# PowerWaveyRadar.net
KiCad netlist of a schematic drawn in Altium Designer
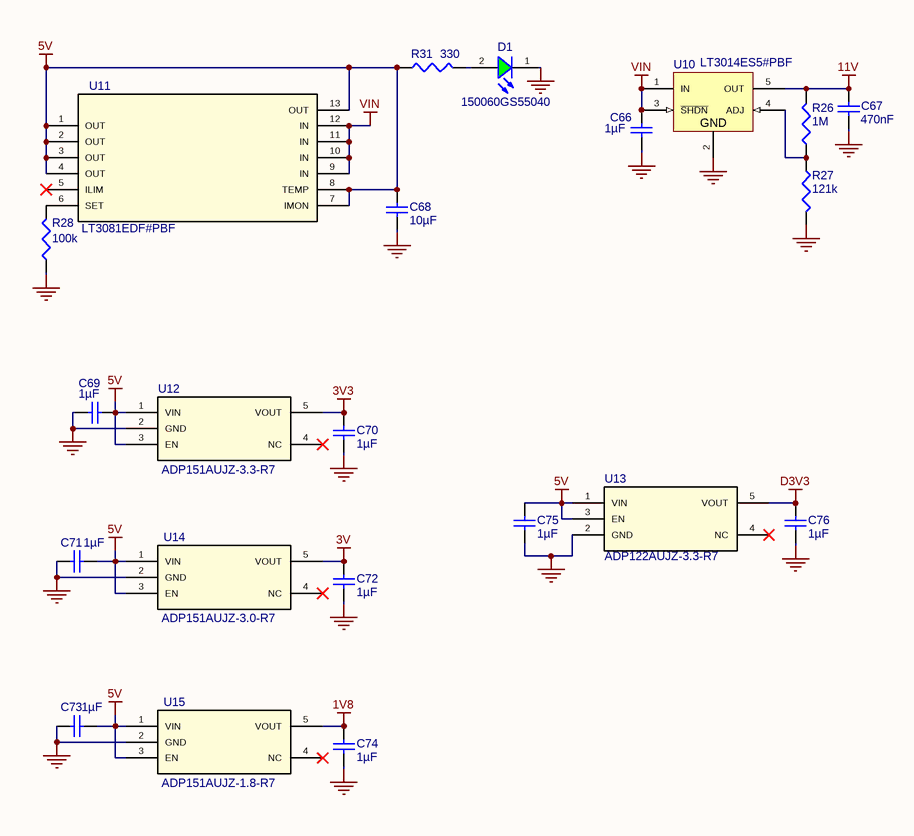
[diagram p0: PowerWaveyRadar.SchDoc]

(export (version "E")
  (design (tool "Eeschema 10.0.6"))
  (components
    (comp (ref "C66")
      (value "1µF")
      (footprint "CAPC0402(1005)60_L")
      (description "Chip Capacitor, 1µF +/-20%, 10V, 0402, Thickness 0.6 mm")
      (fields (field (name "TOLERANCE") "10%") (field (name "Comment") "Capacitor 1µF +/-20% 10V 0402"))
      (libsource (lib "University of South Florida") (part "CAP-NP-2"))
    )
    (comp (ref "C67")
      (value "470nF")
      (footprint "CAPC0402(1005)60_L")
      (description "Chip Capacitor, 470nF +/-40%, 10V, 0402, Thickness 0.6 mm")
      (fields (field (name "TOLERANCE") "20%") (field (name "Comment") "Capacitor 470nF +/-40% 10V 0402"))
      (libsource (lib "University of South Florida") (part "CAP-NP-2"))
    )
    (comp (ref "C68")
      (value "10µF")
      (footprint "CAPC0402(1005)60_L")
      (description "Chip Capacitor, 10µF +/-40%, 6.3V, 0402, Thickness 0.6 mm")
      (fields (field (name "TOLERANCE") "10%") (field (name "Comment") "Capacitor 10µF +/-40% 6.3V 0402"))
      (libsource (lib "University of South Florida") (part "CAP-NP-2"))
    )
    (comp (ref "C69")
      (value "1µF")
      (footprint "CAPC0402(1005)60_L")
      (description "Chip Capacitor, 1µF +/-20%, 10V, 0402, Thickness 0.6 mm")
      (fields (field (name "TOLERANCE") "10%") (field (name "Comment") "Capacitor 1µF +/-20% 10V 0402"))
      (libsource (lib "University of South Florida") (part "CAP-NP-2"))
    )
    (comp (ref "C70")
      (value "1µF")
      (footprint "CAPC0402(1005)60_L")
      (description "Chip Capacitor, 1µF +/-20%, 10V, 0402, Thickness 0.6 mm")
      (fields (field (name "TOLERANCE") "10%") (field (name "Comment") "Capacitor 1µF +/-20% 10V 0402"))
      (libsource (lib "University of South Florida") (part "CAP-NP-2"))
    )
    (comp (ref "C71")
      (value "1µF")
      (footprint "CAPC0402(1005)60_L")
      (description "Chip Capacitor, 1µF +/-20%, 10V, 0402, Thickness 0.6 mm")
      (fields (field (name "TOLERANCE") "10%") (field (name "Comment") "Capacitor 1µF +/-20% 10V 0402"))
      (libsource (lib "University of South Florida") (part "CAP-NP-2"))
    )
    (comp (ref "C72")
      (value "1µF")
      (footprint "CAPC0402(1005)60_L")
      (description "Chip Capacitor, 1µF +/-20%, 10V, 0402, Thickness 0.6 mm")
      (fields (field (name "TOLERANCE") "10%") (field (name "Comment") "Capacitor 1µF +/-20% 10V 0402"))
      (libsource (lib "University of South Florida") (part "CAP-NP-2"))
    )
    (comp (ref "C73")
      (value "1µF")
      (footprint "CAPC0402(1005)60_L")
      (description "Chip Capacitor, 1µF +/-20%, 10V, 0402, Thickness 0.6 mm")
      (fields (field (name "TOLERANCE") "10%") (field (name "Comment") "Capacitor 1µF +/-20% 10V 0402"))
      (libsource (lib "University of South Florida") (part "CAP-NP-2"))
    )
    (comp (ref "C74")
      (value "1µF")
      (footprint "CAPC0402(1005)60_L")
      (description "Chip Capacitor, 1µF +/-20%, 10V, 0402, Thickness 0.6 mm")
      (fields (field (name "TOLERANCE") "10%") (field (name "Comment") "Capacitor 1µF +/-20% 10V 0402"))
      (libsource (lib "University of South Florida") (part "CAP-NP-2"))
    )
    (comp (ref "C75")
      (value "1µF")
      (footprint "CAPC0402(1005)60_L")
      (description "Chip Capacitor, 1µF +/-20%, 10V, 0402, Thickness 0.6 mm")
      (fields (field (name "TOLERANCE") "10%") (field (name "Comment") "Capacitor 1µF +/-20% 10V 0402"))
      (libsource (lib "University of South Florida") (part "CAP-NP-2"))
    )
    (comp (ref "C76")
      (value "1µF")
      (footprint "CAPC0402(1005)60_L")
      (description "Chip Capacitor, 1µF +/-20%, 10V, 0402, Thickness 0.6 mm")
      (fields (field (name "TOLERANCE") "10%") (field (name "Comment") "Capacitor 1µF +/-20% 10V 0402"))
      (libsource (lib "University of South Florida") (part "CAP-NP-2"))
    )
    (comp (ref "D1")
      (value "150060GS55040")
      (footprint "WL-SMCD_0603")
      (description "WL-SMCD SMT Mono-color Chip LED Diffused, size 0603, Green, 3.2V, 140deg")
      (fields (field (name "PUBLISHER") "Wurth Elektronik"))
      (libsource (lib "University of South Florida") (part "150060GS55040"))
    )
    (comp (ref "R26")
      (value "1M")
      (footprint "RESC0402(1005)_L")
      (description "Chip Resistor, 1 MOhms, +/-1 %, 63 mW, -55 to 155 degC, 0402")
      (fields (field (name "POWER") "63mW") (field (name "TOLERANCE") "1%"))
      (libsource (lib "University of South Florida") (part "RES-2"))
    )
    (comp (ref "R27")
      (value "121k")
      (footprint "RESC0402(1005)_L")
      (description "Chip Resistor, 121 kOhms, +/-1 %, 63 mW, -55 to 155 degC, 0402")
      (fields (field (name "POWER") "63mW") (field (name "TOLERANCE") "1%"))
      (libsource (lib "University of South Florida") (part "RES-2"))
    )
    (comp (ref "R28")
      (value "100k")
      (footprint "RESC1005X40X25ML05T05")
      (description "Chip Resistor, 100 KOhm, +/- 1%, 0.1 W, -55 to 155 degC, 0402 (1005 Metric)")
      (fields (field (name "TOLERANCE") "1%") (field (name "POWER") "100mW"))
      (libsource (lib "University of South Florida") (part "RES-2"))
    )
    (comp (ref "R31")
      (value "330")
      (footprint "RESC0402(1005)_L")
      (description "Chip Resistor, 330 Ohms, +/-5 %, 63 mW, -55 to 155 degC, 0402")
      (fields (field (name "POWER") "63mW") (field (name "TOLERANCE") "5%"))
      (libsource (lib "University of South Florida") (part "RES-2"))
    )
    (comp (ref "U10")
      (value "LT3014ES5#PBF")
      (footprint "LT-S5-5-TSOT-23_M")
      (libsource (lib "University of South Florida") (part "LT-LT3014_1761_LTC1844-S5-5"))
    )
    (comp (ref "U11")
      (value "LT3081EDF#PBF")
      (footprint "DFN-12_DF")
      (description "No Description Available")
      (fields
        (field (name "MANUFACTURER_PART_NUMBER") "lt3081edf#pbf")
        (field (name "COPYRIGHT") "Copyright (C) 2018 Accelerated Designs. All rights reserved")
      )
      (libsource (lib "University of South Florida") (part "LT3081EDF#PBF"))
    )
    (comp (ref "U12")
      (value "ADP151AUJZ-3.3-R7")
      (footprint "UJ_5")
      (description "Ultralow Noise, 200 mA, CMOS Linear Regulator")
      (libsource (lib "University of South Florida") (part "ADP151AUJZ-3.3-R7"))
    )
    (comp (ref "U13")
      (value "ADP122AUJZ-3.3-R7")
      (footprint "UJ_5_ADI")
      (description "5.5 V Input, 300 mA, Low Quiescent Current, CMOS Linear Regulator, Fixed Output Voltage")
      (fields (field (name "COPYRIGHT") "Copyright (C) 2021 Accelerated Designs. All rights reserved"))
      (libsource (lib "University of South Florida") (part "ADP122AUJZ-3.3-R7"))
    )
    (comp (ref "U14")
      (value "ADP151AUJZ-3.0-R7")
      (footprint "UJ_5")
      (description "Ultralow Noise, 200 mA, CMOS Linear Regulator")
      (libsource (lib "University of South Florida") (part "ADP151AUJZ-3.0-R7"))
    )
    (comp (ref "U15")
      (value "ADP151AUJZ-1.8-R7")
      (footprint "UJ_5")
      (description "Ultralow Noise, 200 mA, CMOS Linear Regulator")
      (libsource (lib "University of South Florida") (part "ADP151AUJZ-1.8-R7"))
    )
  )
  (nets
    (net (code "1") (name "1V8") (class "Default")
      (node (ref "C74") (pin "1") (pinfunction "1_1") (pintype "passive"))
      (node (ref "U15") (pin "5") (pinfunction "VOUT_5") (pintype "passive"))
    )
    (net (code "2") (name "3V") (class "Default")
      (node (ref "C72") (pin "2") (pinfunction "2_2") (pintype "passive"))
      (node (ref "U14") (pin "5") (pinfunction "VOUT_5") (pintype "passive"))
    )
    (net (code "3") (name "3V3") (class "Default")
      (node (ref "C70") (pin "1") (pinfunction "1_1") (pintype "passive"))
      (node (ref "U12") (pin "5") (pinfunction "VOUT_5") (pintype "passive"))
    )
    (net (code "4") (name "5V") (class "Default")
      (node (ref "C68") (pin "2") (pinfunction "2_2") (pintype "passive"))
      (node (ref "C69") (pin "1") (pinfunction "1_1") (pintype "passive"))
      (node (ref "C71") (pin "2") (pinfunction "2_2") (pintype "passive"))
      (node (ref "C73") (pin "2") (pinfunction "2_2") (pintype "passive"))
      (node (ref "C75") (pin "2") (pinfunction "2_2") (pintype "passive"))
      (node (ref "R31") (pin "1") (pinfunction "1_1") (pintype "passive"))
      (node (ref "U11") (pin "1") (pinfunction "OUT_1") (pintype "power_in"))
      (node (ref "U11") (pin "13") (pinfunction "OUT_13") (pintype "power_in"))
      (node (ref "U11") (pin "2") (pinfunction "OUT_2") (pintype "power_in"))
      (node (ref "U11") (pin "3") (pinfunction "OUT_3") (pintype "power_in"))
      (node (ref "U11") (pin "4") (pinfunction "OUT_4") (pintype "power_in"))
      (node (ref "U11") (pin "7") (pinfunction "IMON_7") (pintype "passive"))
      (node (ref "U11") (pin "8") (pinfunction "TEMP_8") (pintype "passive"))
      (node (ref "U12") (pin "1") (pinfunction "VIN_1") (pintype "passive"))
      (node (ref "U12") (pin "3") (pinfunction "EN_3") (pintype "passive"))
      (node (ref "U13") (pin "1") (pinfunction "VIN_1") (pintype "passive"))
      (node (ref "U13") (pin "3") (pinfunction "EN_3") (pintype "passive"))
      (node (ref "U14") (pin "1") (pinfunction "VIN_1") (pintype "passive"))
      (node (ref "U14") (pin "3") (pinfunction "EN_3") (pintype "passive"))
      (node (ref "U15") (pin "1") (pinfunction "VIN_1") (pintype "passive"))
      (node (ref "U15") (pin "3") (pinfunction "EN_3") (pintype "passive"))
    )
    (net (code "5") (name "11V") (class "Default")
      (node (ref "C67") (pin "2") (pinfunction "2_2") (pintype "passive"))
      (node (ref "R26") (pin "2") (pinfunction "2_2") (pintype "passive"))
      (node (ref "U10") (pin "5") (pinfunction "OUT_5") (pintype "power_in"))
    )
    (net (code "6") (name "D3V3") (class "Default")
      (node (ref "C76") (pin "2") (pinfunction "2_2") (pintype "passive"))
      (node (ref "U13") (pin "5") (pinfunction "VOUT_5") (pintype "passive"))
    )
    (net (code "7") (name "GND") (class "Default")
      (node (ref "C66") (pin "1") (pinfunction "1_1") (pintype "passive"))
      (node (ref "C67") (pin "1") (pinfunction "1_1") (pintype "passive"))
      (node (ref "C68") (pin "1") (pinfunction "1_1") (pintype "passive"))
      (node (ref "C69") (pin "2") (pinfunction "2_2") (pintype "passive"))
      (node (ref "C70") (pin "2") (pinfunction "2_2") (pintype "passive"))
      (node (ref "C71") (pin "1") (pinfunction "1_1") (pintype "passive"))
      (node (ref "C72") (pin "1") (pinfunction "1_1") (pintype "passive"))
      (node (ref "C73") (pin "1") (pinfunction "1_1") (pintype "passive"))
      (node (ref "C74") (pin "2") (pinfunction "2_2") (pintype "passive"))
      (node (ref "C75") (pin "1") (pinfunction "1_1") (pintype "passive"))
      (node (ref "C76") (pin "1") (pinfunction "1_1") (pintype "passive"))
      (node (ref "D1") (pin "1") (pinfunction "K_1") (pintype "passive"))
      (node (ref "R27") (pin "2") (pinfunction "2_2") (pintype "passive"))
      (node (ref "R28") (pin "1") (pinfunction "1_1") (pintype "passive"))
      (node (ref "U10") (pin "2") (pinfunction "GND_2") (pintype "power_in"))
      (node (ref "U12") (pin "2") (pinfunction "GND_2") (pintype "passive"))
      (node (ref "U13") (pin "2") (pinfunction "GND_2") (pintype "passive"))
      (node (ref "U14") (pin "2") (pinfunction "GND_2") (pintype "passive"))
      (node (ref "U15") (pin "2") (pinfunction "GND_2") (pintype "passive"))
    )
    (net (code "8") (name "Net-(D1-A)") (class "Default")
      (node (ref "D1") (pin "2") (pinfunction "A_2") (pintype "passive"))
      (node (ref "R31") (pin "2") (pinfunction "2_2") (pintype "passive"))
    )
    (net (code "9") (name "Net-(U10-ADJ)") (class "Default")
      (node (ref "R26") (pin "1") (pinfunction "1_1") (pintype "passive"))
      (node (ref "R27") (pin "1") (pinfunction "1_1") (pintype "passive"))
      (node (ref "U10") (pin "4") (pinfunction "ADJ_4") (pintype "input"))
    )
    (net (code "10") (name "Net-(U11-SET)") (class "Default")
      (node (ref "R28") (pin "2") (pinfunction "2_2") (pintype "passive"))
      (node (ref "U11") (pin "6") (pinfunction "SET_6") (pintype "passive"))
    )
    (net (code "11") (name "VIN") (class "Default")
      (node (ref "C66") (pin "2") (pinfunction "2_2") (pintype "passive"))
      (node (ref "U10") (pin "1") (pinfunction "IN_1") (pintype "power_in"))
      (node (ref "U10") (pin "3") (pinfunction "~{SHDN}_3") (pintype "input"))
      (node (ref "U11") (pin "10") (pinfunction "IN_10") (pintype "power_in"))
      (node (ref "U11") (pin "11") (pinfunction "IN_11") (pintype "power_in"))
      (node (ref "U11") (pin "12") (pinfunction "IN_12") (pintype "power_in"))
      (node (ref "U11") (pin "9") (pinfunction "IN_9") (pintype "power_in"))
    )
    (net (code "12") (name "unconnected-(U11-ILIM-Pad5)") (class "Default")
      (node (ref "U11") (pin "5") (pinfunction "ILIM_5") (pintype "passive+no_connect"))
    )
    (net (code "13") (name "unconnected-(U12-NC-Pad4)") (class "Default")
      (node (ref "U12") (pin "4") (pinfunction "NC_4") (pintype "passive+no_connect"))
    )
    (net (code "14") (name "unconnected-(U13-NC-Pad4)") (class "Default")
      (node (ref "U13") (pin "4") (pinfunction "NC_4") (pintype "passive+no_connect"))
    )
    (net (code "15") (name "unconnected-(U14-NC-Pad4)") (class "Default")
      (node (ref "U14") (pin "4") (pinfunction "NC_4") (pintype "passive+no_connect"))
    )
    (net (code "16") (name "unconnected-(U15-NC-Pad4)") (class "Default")
      (node (ref "U15") (pin "4") (pinfunction "NC_4") (pintype "passive+no_connect"))
    )
  )
)
